# integracion2025.net
KiCad netlist of a schematic drawn in EasyEDA
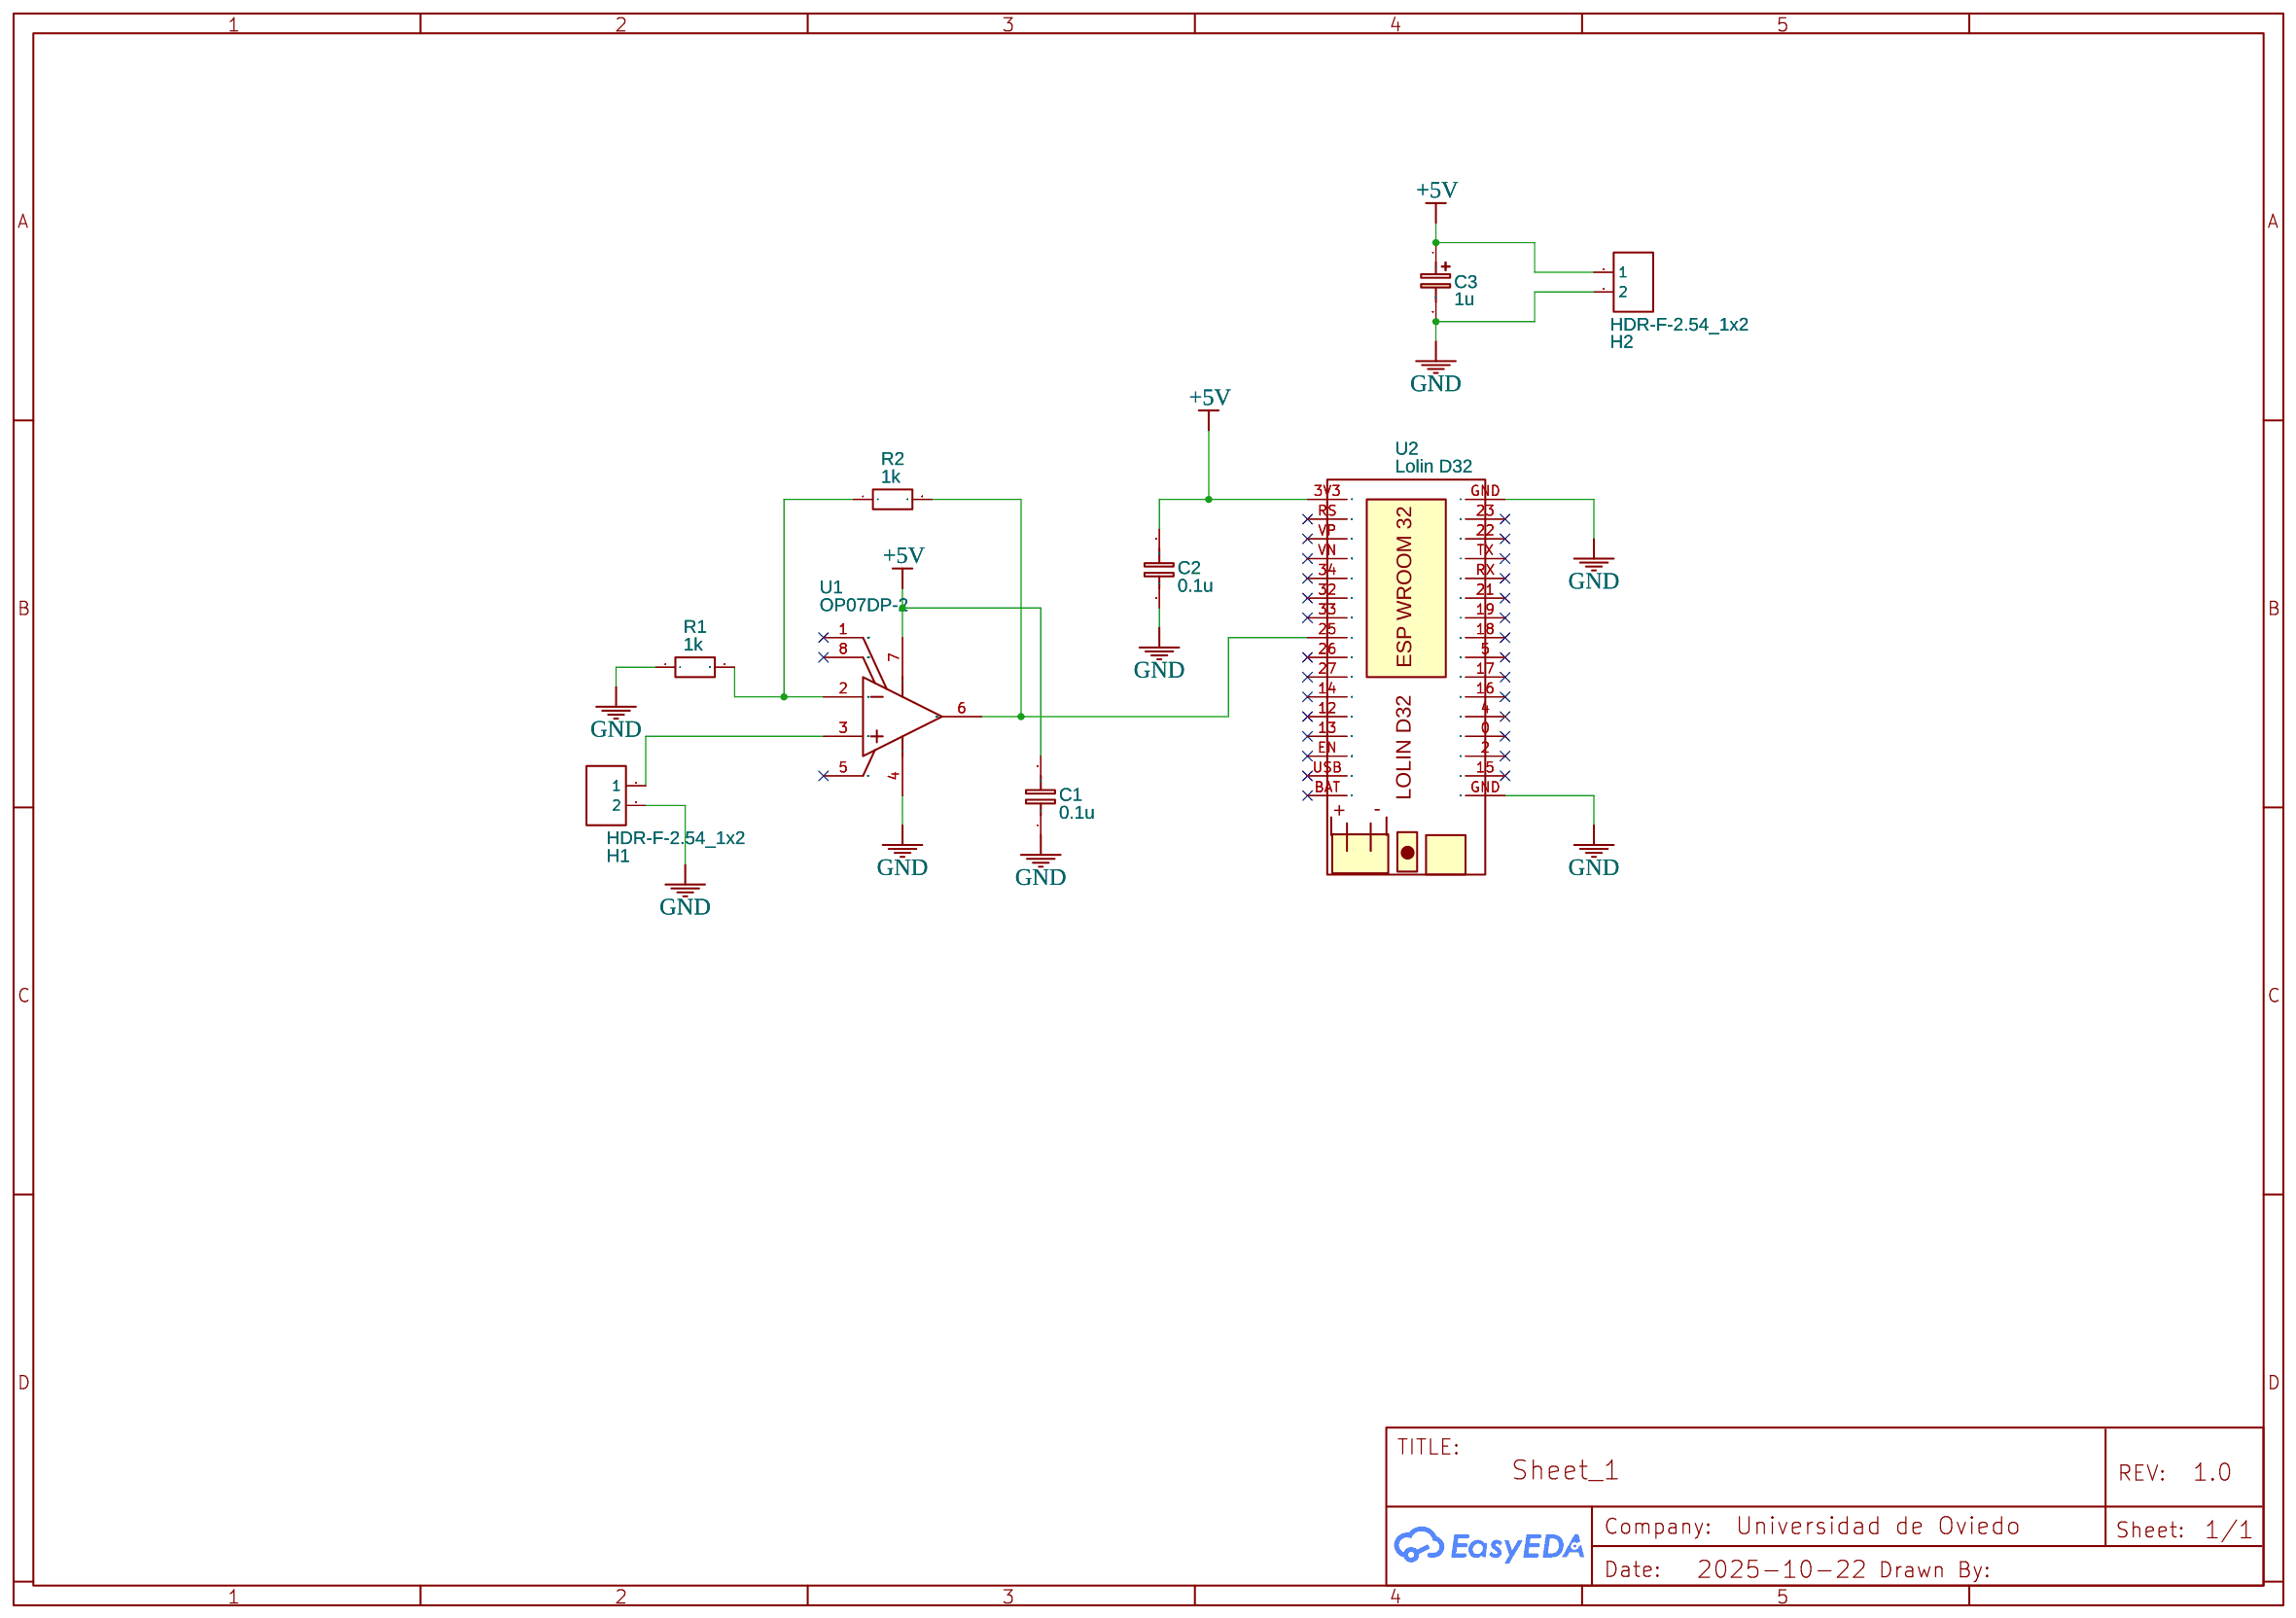
[diagram p0: schematic sheet]

(export (version "E")
  (design (tool "Eeschema 10.0.6"))
  (components
    (comp (ref "C1") (value "0.1u") (libsource (lib "") (part "C_0603_EU_1")))
    (comp (ref "C2") (value "0.1u") (libsource (lib "") (part "C_0603_EU")))
    (comp (ref "C3") (value "1u") (libsource (lib "") (part "C_Tan_SMD_A_EU")))
    (comp (ref "H1") (value "HDR-F-2.54_1x2") (libsource (lib "") (part "HDR-F-2.54_1x2_1")))
    (comp (ref "H2") (value "HDR-F-2.54_1x2") (libsource (lib "") (part "HDR-F-2.54_1x2")))
    (comp (ref "R1") (value "1k") (libsource (lib "") (part "R_0603_EU")))
    (comp (ref "R2") (value "1k") (libsource (lib "") (part "R_0603_EU")))
    (comp (ref "U1")
      (value "OP07DP-2")
      (fields (field (name "Manufacturer") "ADI(亚德诺)/MAXIM(美信)"))
      (libsource (lib "") (part "OP07DP-2"))
    )
    (comp (ref "U2")
      (value "Lolin D32")
      (fields (field (name "Manufacturer Part") "New SchematicLib"))
      (libsource (lib "") (part "Lolin D32"))
    )
  )
  (nets
    (net (code "1") (name "+5V") (class "Default")
      (node (ref "C1") (pin "2") (pinfunction "2_2") (pintype "unspecified"))
      (node (ref "C2") (pin "2") (pinfunction "2_2") (pintype "unspecified"))
      (node (ref "C3") (pin "1") (pinfunction "1_1") (pintype "unspecified"))
      (node (ref "H2") (pin "1") (pinfunction "1_1") (pintype "input"))
      (node (ref "U1") (pin "7") (pinfunction "V+_7") (pintype "passive"))
      (node (ref "U2") (pin "3V3") (pinfunction "17_3V3") (pintype "unspecified"))
    )
    (net (code "2") (name "GND") (class "Default")
      (node (ref "C1") (pin "1") (pinfunction "1_1") (pintype "unspecified"))
      (node (ref "C2") (pin "1") (pinfunction "1_1") (pintype "unspecified"))
      (node (ref "C3") (pin "2") (pinfunction "2_2") (pintype "unspecified"))
      (node (ref "H1") (pin "2") (pinfunction "2_2") (pintype "input"))
      (node (ref "H2") (pin "2") (pinfunction "2_2") (pintype "input"))
      (node (ref "R1") (pin "1") (pinfunction "1_1") (pintype "unspecified"))
      (node (ref "U1") (pin "4") (pinfunction "V-_4") (pintype "passive"))
      (node (ref "U2") (pin "GND") (pinfunction "16_GND") (pintype "unspecified"))
    )
    (net (code "3") (name "Net-(U1-+IN_A)") (class "Default")
      (node (ref "H1") (pin "1") (pinfunction "1_1") (pintype "input"))
      (node (ref "U1") (pin "3") (pinfunction "+IN_A_3") (pintype "unspecified"))
    )
    (net (code "4") (name "Net-(U1--IN_A)") (class "Default")
      (node (ref "R1") (pin "2") (pinfunction "2_2") (pintype "unspecified"))
      (node (ref "R2") (pin "1") (pinfunction "1_1") (pintype "unspecified"))
      (node (ref "U1") (pin "2") (pinfunction "-IN_A_2") (pintype "unspecified"))
    )
    (net (code "5") (name "Net-(U1-OUT_A)") (class "Default")
      (node (ref "R2") (pin "2") (pinfunction "2_2") (pintype "unspecified"))
      (node (ref "U1") (pin "6") (pinfunction "OUT_A_6") (pintype "output"))
      (node (ref "U2") (pin "25") (pinfunction "24_25") (pintype "unspecified"))
    )
    (net (code "6") (name "unconnected-(U1-NC-Pad5)") (class "Default")
      (node (ref "U1") (pin "5") (pinfunction "NC_5") (pintype "unspecified+no_connect"))
    )
    (net (code "7") (name "unconnected-(U1-VOS_TRIM-Pad1)") (class "Default")
      (node (ref "U1") (pin "1") (pinfunction "VOS_TRIM_1") (pintype "unspecified+no_connect"))
    )
    (net (code "8") (name "unconnected-(U1-VOS_TRIM-Pad8)") (class "Default")
      (node (ref "U1") (pin "8") (pinfunction "VOS_TRIM_8") (pintype "unspecified+no_connect"))
    )
    (net (code "9") (name "unconnected-(U2-2-Pad23)") (class "Default")
      (node (ref "U2") (pin "23") (pinfunction "2_23") (pintype "unspecified+no_connect"))
    )
    (net (code "10") (name "unconnected-(U2-3-Pad22)") (class "Default")
      (node (ref "U2") (pin "22") (pinfunction "3_22") (pintype "unspecified+no_connect"))
    )
    (net (code "11") (name "unconnected-(U2-4-PadTX)") (class "Default")
      (node (ref "U2") (pin "TX") (pinfunction "4_TX") (pintype "unspecified+no_connect"))
    )
    (net (code "12") (name "unconnected-(U2-5-PadRX)") (class "Default")
      (node (ref "U2") (pin "RX") (pinfunction "5_RX") (pintype "unspecified+no_connect"))
    )
    (net (code "13") (name "unconnected-(U2-6-Pad21)") (class "Default")
      (node (ref "U2") (pin "21") (pinfunction "6_21") (pintype "unspecified+no_connect"))
    )
    (net (code "14") (name "unconnected-(U2-7-Pad19)") (class "Default")
      (node (ref "U2") (pin "19") (pinfunction "7_19") (pintype "unspecified+no_connect"))
    )
    (net (code "15") (name "unconnected-(U2-8-Pad18)") (class "Default")
      (node (ref "U2") (pin "18") (pinfunction "8_18") (pintype "unspecified+no_connect"))
    )
    (net (code "16") (name "unconnected-(U2-9-Pad5)") (class "Default")
      (node (ref "U2") (pin "5") (pinfunction "9_5") (pintype "unspecified+no_connect"))
    )
    (net (code "17") (name "unconnected-(U2-10-Pad17)") (class "Default")
      (node (ref "U2") (pin "17") (pinfunction "10_17") (pintype "unspecified+no_connect"))
    )
    (net (code "18") (name "unconnected-(U2-11-Pad16)") (class "Default")
      (node (ref "U2") (pin "16") (pinfunction "11_16") (pintype "unspecified+no_connect"))
    )
    (net (code "19") (name "unconnected-(U2-12-Pad4)") (class "Default")
      (node (ref "U2") (pin "4") (pinfunction "12_4") (pintype "unspecified+no_connect"))
    )
    (net (code "20") (name "unconnected-(U2-13-Pad0)") (class "Default")
      (node (ref "U2") (pin "0") (pinfunction "13_0") (pintype "unspecified+no_connect"))
    )
    (net (code "21") (name "unconnected-(U2-14-Pad2)") (class "Default")
      (node (ref "U2") (pin "2") (pinfunction "14_2") (pintype "unspecified+no_connect"))
    )
    (net (code "22") (name "unconnected-(U2-18-PadRS)") (class "Default")
      (node (ref "U2") (pin "RS") (pinfunction "18_RS") (pintype "unspecified+no_connect"))
    )
    (net (code "23") (name "unconnected-(U2-19-PadVP)") (class "Default")
      (node (ref "U2") (pin "VP") (pinfunction "19_VP") (pintype "unspecified+no_connect"))
    )
    (net (code "24") (name "unconnected-(U2-20-PadVN)") (class "Default")
      (node (ref "U2") (pin "VN") (pinfunction "20_VN") (pintype "unspecified+no_connect"))
    )
    (net (code "25") (name "unconnected-(U2-21-Pad34)") (class "Default")
      (node (ref "U2") (pin "34") (pinfunction "21_34") (pintype "unspecified+no_connect"))
    )
    (net (code "26") (name "unconnected-(U2-22-Pad32)") (class "Default")
      (node (ref "U2") (pin "32") (pinfunction "22_32") (pintype "unspecified+no_connect"))
    )
    (net (code "27") (name "unconnected-(U2-23-Pad33)") (class "Default")
      (node (ref "U2") (pin "33") (pinfunction "23_33") (pintype "unspecified+no_connect"))
    )
    (net (code "28") (name "unconnected-(U2-25-Pad26)") (class "Default")
      (node (ref "U2") (pin "26") (pinfunction "25_26") (pintype "unspecified+no_connect"))
    )
    (net (code "29") (name "unconnected-(U2-26-Pad27)") (class "Default")
      (node (ref "U2") (pin "27") (pinfunction "26_27") (pintype "unspecified+no_connect"))
    )
    (net (code "30") (name "unconnected-(U2-27-Pad14)") (class "Default")
      (node (ref "U2") (pin "14") (pinfunction "27_14") (pintype "unspecified+no_connect"))
    )
    (net (code "31") (name "unconnected-(U2-28-Pad12)") (class "Default")
      (node (ref "U2") (pin "12") (pinfunction "28_12") (pintype "unspecified+no_connect"))
    )
    (net (code "32") (name "unconnected-(U2-29-Pad13)") (class "Default")
      (node (ref "U2") (pin "13") (pinfunction "29_13") (pintype "unspecified+no_connect"))
    )
    (net (code "33") (name "unconnected-(U2-30-PadEN)") (class "Default")
      (node (ref "U2") (pin "EN") (pinfunction "30_EN") (pintype "unspecified+no_connect"))
    )
    (net (code "34") (name "unconnected-(U2-31-PadUSB)") (class "Default")
      (node (ref "U2") (pin "USB") (pinfunction "31_USB") (pintype "unspecified+no_connect"))
    )
    (net (code "35") (name "unconnected-(U2-32-PadBAT)") (class "Default")
      (node (ref "U2") (pin "BAT") (pinfunction "32_BAT") (pintype "unspecified+no_connect"))
    )
    (net (code "36") (name "unconnected-(U2-Pad15)") (class "Default")
      (node (ref "U2") (pin "15") (pinfunction "15_15") (pintype "unspecified+no_connect"))
    )
  )
)
